# di.net
KiCad netlist of a schematic drawn in Altium Designer
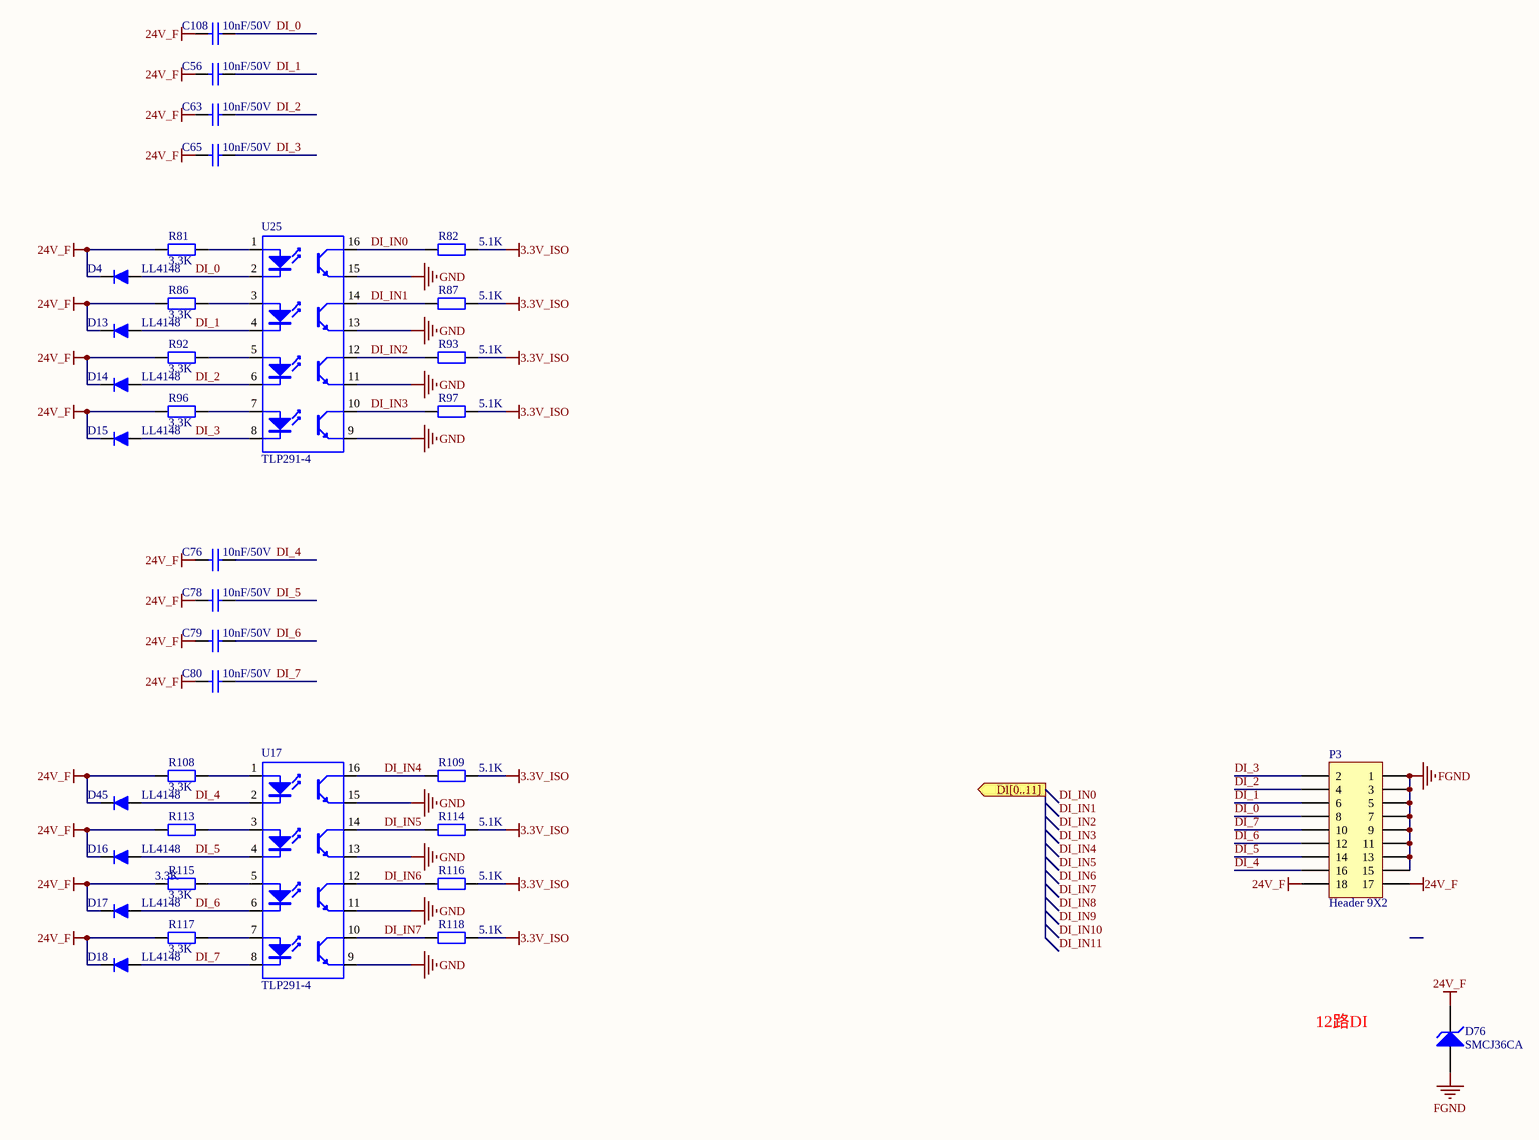
[diagram p0: di.SchDoc]

(export (version "E")
  (design (tool "Eeschema 10.0.6"))
  (components
    (comp (ref "C56")
      (value "10nF/50V")
      (footprint "0603C")
      (description "Capacitor")
      (fields (field (name "PUBLISHER") "Altium Limited"))
      (libsource (lib "Miscellaneous Devices") (part "Cap"))
    )
    (comp (ref "C63")
      (value "10nF/50V")
      (footprint "0603C")
      (description "Capacitor")
      (fields (field (name "PUBLISHER") "Altium Limited"))
      (libsource (lib "Miscellaneous Devices") (part "Cap"))
    )
    (comp (ref "C65")
      (value "10nF/50V")
      (footprint "0603C")
      (description "Capacitor")
      (fields (field (name "PUBLISHER") "Altium Limited"))
      (libsource (lib "Miscellaneous Devices") (part "Cap"))
    )
    (comp (ref "C76")
      (value "10nF/50V")
      (footprint "0603C")
      (description "Capacitor")
      (fields (field (name "PUBLISHER") "Altium Limited"))
      (libsource (lib "Miscellaneous Devices") (part "Cap"))
    )
    (comp (ref "C78")
      (value "10nF/50V")
      (footprint "0603C")
      (description "Capacitor")
      (fields (field (name "PUBLISHER") "Altium Limited"))
      (libsource (lib "Miscellaneous Devices") (part "Cap"))
    )
    (comp (ref "C79")
      (value "10nF/50V")
      (footprint "0603C")
      (description "Capacitor")
      (fields (field (name "PUBLISHER") "Altium Limited"))
      (libsource (lib "Miscellaneous Devices") (part "Cap"))
    )
    (comp (ref "C80")
      (value "10nF/50V")
      (footprint "0603C")
      (description "Capacitor")
      (fields (field (name "PUBLISHER") "Altium Limited"))
      (libsource (lib "Miscellaneous Devices") (part "Cap"))
    )
    (comp (ref "C108")
      (value "10nF/50V")
      (footprint "0603C")
      (description "Capacitor")
      (fields (field (name "PUBLISHER") "Altium Limited"))
      (libsource (lib "Miscellaneous Devices") (part "Cap"))
    )
    (comp (ref "D4")
      (value "LL4148")
      (footprint "DO-213AB/LL34/MiniMELF")
      (description "VISHAY,LL4148,圆柱体MiniMELF100V/2A,ROHS")
      (libsource (lib "Device2018") (part "LL4148"))
    )
    (comp (ref "D13")
      (value "LL4148")
      (footprint "DO-213AB/LL34/MiniMELF")
      (description "VISHAY,LL4148,圆柱体MiniMELF100V/2A,ROHS")
      (libsource (lib "Device2018") (part "LL4148"))
    )
    (comp (ref "D14")
      (value "LL4148")
      (footprint "DO-213AB/LL34/MiniMELF")
      (description "VISHAY,LL4148,圆柱体MiniMELF100V/2A,ROHS")
      (libsource (lib "Device2018") (part "LL4148"))
    )
    (comp (ref "D15")
      (value "LL4148")
      (footprint "DO-213AB/LL34/MiniMELF")
      (description "VISHAY,LL4148,圆柱体MiniMELF100V/2A,ROHS")
      (libsource (lib "Device2018") (part "LL4148"))
    )
    (comp (ref "D16")
      (value "LL4148")
      (footprint "DO-213AB/LL34/MiniMELF")
      (description "VISHAY,LL4148,圆柱体MiniMELF100V/2A,ROHS")
      (libsource (lib "Device2018") (part "LL4148"))
    )
    (comp (ref "D17")
      (value "LL4148")
      (footprint "DO-213AB/LL34/MiniMELF")
      (description "VISHAY,LL4148,圆柱体MiniMELF100V/2A,ROHS")
      (libsource (lib "Device2018") (part "LL4148"))
    )
    (comp (ref "D18")
      (value "LL4148")
      (footprint "DO-213AB/LL34/MiniMELF")
      (description "VISHAY,LL4148,圆柱体MiniMELF100V/2A,ROHS")
      (libsource (lib "Device2018") (part "LL4148"))
    )
    (comp (ref "D45")
      (value "LL4148")
      (footprint "DO-213AB/LL34/MiniMELF")
      (description "VISHAY,LL4148,圆柱体MiniMELF100V/2A,ROHS")
      (libsource (lib "Device2018") (part "LL4148"))
    )
    (comp (ref "D76")
      (value "SMCJ36CA")
      (footprint "smc")
      (description "SMBJ36CA")
      (fields (field (name "PUBLISHER") "Altium Limited"))
      (libsource (lib "Miscellaneous Devices") (part "D Zener"))
    )
    (comp (ref "P3")
      (value "Header 9X2")
      (footprint "XH2.54_2x9")
      (description "Header, 9-Pin, Dual row")
      (fields (field (name "PUBLISHER") "Altium Limited"))
      (libsource (lib "Miscellaneous Connectors") (part "Header 9X2"))
    )
    (comp (ref "R81") (value "3.3K") (footprint "0603R") (libsource (lib "MQlibrary") (part "Res0805M")))
    (comp (ref "R82") (value "5.1K") (footprint "0603R") (libsource (lib "MQlibrary") (part "Res0805M")))
    (comp (ref "R86") (value "3.3K") (footprint "0603R") (libsource (lib "MQlibrary") (part "Res0805M")))
    (comp (ref "R87") (value "5.1K") (footprint "0603R") (libsource (lib "MQlibrary") (part "Res0805M")))
    (comp (ref "R92") (value "3.3K") (footprint "0603R") (libsource (lib "MQlibrary") (part "Res0805M")))
    (comp (ref "R93") (value "5.1K") (footprint "0603R") (libsource (lib "MQlibrary") (part "Res0805M")))
    (comp (ref "R96") (value "3.3K") (footprint "0603R") (libsource (lib "MQlibrary") (part "Res0805M")))
    (comp (ref "R97") (value "5.1K") (footprint "0603R") (libsource (lib "MQlibrary") (part "Res0805M")))
    (comp (ref "R108") (value "3.3K") (footprint "0603R") (libsource (lib "MQlibrary") (part "Res0805M")))
    (comp (ref "R109") (value "5.1K") (footprint "0603R") (libsource (lib "MQlibrary") (part "Res0805M")))
    (comp (ref "R113") (value "3.3K") (footprint "0603R") (libsource (lib "MQlibrary") (part "Res0805M")))
    (comp (ref "R114") (value "5.1K") (footprint "0603R") (libsource (lib "MQlibrary") (part "Res0805M")))
    (comp (ref "R115") (value "3.3K") (footprint "0603R") (libsource (lib "MQlibrary") (part "Res0805M")))
    (comp (ref "R116") (value "5.1K") (footprint "0603R") (libsource (lib "MQlibrary") (part "Res0805M")))
    (comp (ref "R117") (value "3.3K") (footprint "0603R") (libsource (lib "MQlibrary") (part "Res0805M")))
    (comp (ref "R118") (value "5.1K") (footprint "0603R") (libsource (lib "MQlibrary") (part "Res0805M")))
    (comp (ref "U17") (value "TLP291-4") (footprint "SOP16-T") (libsource (lib "DI16") (part "TLP281-4")))
    (comp (ref "U25") (value "TLP291-4") (footprint "SOP16-T") (libsource (lib "DI16") (part "TLP281-4")))
  )
  (nets
    (net (code "14") (name "/DI_0") (class "Default")
      (node (ref "C108") (pin "2") (pinfunction "2_2") (pintype "passive"))
      (node (ref "D4") (pin "1") (pinfunction "2_1") (pintype "passive"))
      (node (ref "P3") (pin "8") (pinfunction "8_8") (pintype "passive"))
      (node (ref "U25") (pin "2") (pinfunction "K_2") (pintype "passive"))
    )
    (net (code "15") (name "/DI_1") (class "Default")
      (node (ref "C56") (pin "2") (pinfunction "2_2") (pintype "passive"))
      (node (ref "D13") (pin "1") (pinfunction "2_1") (pintype "passive"))
      (node (ref "P3") (pin "6") (pinfunction "6_6") (pintype "passive"))
      (node (ref "U25") (pin "4") (pinfunction "K_4") (pintype "passive"))
    )
    (net (code "16") (name "/DI_2") (class "Default")
      (node (ref "C63") (pin "2") (pinfunction "2_2") (pintype "passive"))
      (node (ref "D14") (pin "1") (pinfunction "2_1") (pintype "passive"))
      (node (ref "P3") (pin "4") (pinfunction "4_4") (pintype "passive"))
      (node (ref "U25") (pin "6") (pinfunction "K_6") (pintype "passive"))
    )
    (net (code "17") (name "/DI_3") (class "Default")
      (node (ref "C65") (pin "2") (pinfunction "2_2") (pintype "passive"))
      (node (ref "D15") (pin "1") (pinfunction "2_1") (pintype "passive"))
      (node (ref "P3") (pin "2") (pinfunction "2_2") (pintype "passive"))
      (node (ref "U25") (pin "8") (pinfunction "K_8") (pintype "passive"))
    )
    (net (code "18") (name "/DI_4") (class "Default")
      (node (ref "C76") (pin "2") (pinfunction "2_2") (pintype "passive"))
      (node (ref "D45") (pin "1") (pinfunction "2_1") (pintype "passive"))
      (node (ref "P3") (pin "16") (pinfunction "16_16") (pintype "passive"))
      (node (ref "U17") (pin "2") (pinfunction "K_2") (pintype "passive"))
    )
    (net (code "19") (name "/DI_5") (class "Default")
      (node (ref "C78") (pin "2") (pinfunction "2_2") (pintype "passive"))
      (node (ref "D16") (pin "1") (pinfunction "2_1") (pintype "passive"))
      (node (ref "P3") (pin "14") (pinfunction "14_14") (pintype "passive"))
      (node (ref "U17") (pin "4") (pinfunction "K_4") (pintype "passive"))
    )
    (net (code "20") (name "/DI_6") (class "Default")
      (node (ref "C79") (pin "2") (pinfunction "2_2") (pintype "passive"))
      (node (ref "D17") (pin "1") (pinfunction "2_1") (pintype "passive"))
      (node (ref "P3") (pin "12") (pinfunction "12_12") (pintype "passive"))
      (node (ref "U17") (pin "6") (pinfunction "K_6") (pintype "passive"))
    )
    (net (code "21") (name "/DI_7") (class "Default")
      (node (ref "C80") (pin "2") (pinfunction "2_2") (pintype "passive"))
      (node (ref "D18") (pin "1") (pinfunction "2_1") (pintype "passive"))
      (node (ref "P3") (pin "10") (pinfunction "10_10") (pintype "passive"))
      (node (ref "U17") (pin "8") (pinfunction "K_8") (pintype "passive"))
    )
    (net (code "22") (name "/DI_IN0") (class "Default")
      (node (ref "R82") (pin "2") (pinfunction "2_2") (pintype "passive"))
      (node (ref "U25") (pin "16") (pinfunction "C_16") (pintype "passive"))
    )
    (net (code "23") (name "/DI_IN1") (class "Default")
      (node (ref "R87") (pin "2") (pinfunction "2_2") (pintype "passive"))
      (node (ref "U25") (pin "14") (pinfunction "C_14") (pintype "passive"))
    )
    (net (code "24") (name "/DI_IN2") (class "Default")
      (node (ref "R93") (pin "2") (pinfunction "2_2") (pintype "passive"))
      (node (ref "U25") (pin "12") (pinfunction "C_12") (pintype "passive"))
    )
    (net (code "25") (name "/DI_IN3") (class "Default")
      (node (ref "R97") (pin "2") (pinfunction "2_2") (pintype "passive"))
      (node (ref "U25") (pin "10") (pinfunction "C_10") (pintype "passive"))
    )
    (net (code "26") (name "/DI_IN4") (class "Default")
      (node (ref "R109") (pin "2") (pinfunction "2_2") (pintype "passive"))
      (node (ref "U17") (pin "16") (pinfunction "C_16") (pintype "passive"))
    )
    (net (code "27") (name "/DI_IN5") (class "Default")
      (node (ref "R114") (pin "2") (pinfunction "2_2") (pintype "passive"))
      (node (ref "U17") (pin "14") (pinfunction "C_14") (pintype "passive"))
    )
    (net (code "28") (name "/DI_IN6") (class "Default")
      (node (ref "R116") (pin "2") (pinfunction "2_2") (pintype "passive"))
      (node (ref "U17") (pin "12") (pinfunction "C_12") (pintype "passive"))
    )
    (net (code "29") (name "/DI_IN7") (class "Default")
      (node (ref "R118") (pin "2") (pinfunction "2_2") (pintype "passive"))
      (node (ref "U17") (pin "10") (pinfunction "C_10") (pintype "passive"))
    )
    (net (code "34") (name "3.3V_ISO") (class "Default")
      (node (ref "R109") (pin "1") (pinfunction "1_1") (pintype "passive"))
      (node (ref "R114") (pin "1") (pinfunction "1_1") (pintype "passive"))
      (node (ref "R116") (pin "1") (pinfunction "1_1") (pintype "passive"))
      (node (ref "R118") (pin "1") (pinfunction "1_1") (pintype "passive"))
      (node (ref "R82") (pin "1") (pinfunction "1_1") (pintype "passive"))
      (node (ref "R87") (pin "1") (pinfunction "1_1") (pintype "passive"))
      (node (ref "R93") (pin "1") (pinfunction "1_1") (pintype "passive"))
      (node (ref "R97") (pin "1") (pinfunction "1_1") (pintype "passive"))
    )
    (net (code "35") (name "24V_F") (class "Default")
      (node (ref "C108") (pin "1") (pinfunction "1_1") (pintype "passive"))
      (node (ref "C56") (pin "1") (pinfunction "1_1") (pintype "passive"))
      (node (ref "C63") (pin "1") (pinfunction "1_1") (pintype "passive"))
      (node (ref "C65") (pin "1") (pinfunction "1_1") (pintype "passive"))
      (node (ref "C76") (pin "1") (pinfunction "1_1") (pintype "passive"))
      (node (ref "C78") (pin "1") (pinfunction "1_1") (pintype "passive"))
      (node (ref "C79") (pin "1") (pinfunction "1_1") (pintype "passive"))
      (node (ref "C80") (pin "1") (pinfunction "1_1") (pintype "passive"))
      (node (ref "D13") (pin "2") (pinfunction "1_2") (pintype "passive"))
      (node (ref "D14") (pin "2") (pinfunction "1_2") (pintype "passive"))
      (node (ref "D15") (pin "2") (pinfunction "1_2") (pintype "passive"))
      (node (ref "D16") (pin "2") (pinfunction "1_2") (pintype "passive"))
      (node (ref "D17") (pin "2") (pinfunction "1_2") (pintype "passive"))
      (node (ref "D18") (pin "2") (pinfunction "1_2") (pintype "passive"))
      (node (ref "D4") (pin "2") (pinfunction "1_2") (pintype "passive"))
      (node (ref "D45") (pin "2") (pinfunction "1_2") (pintype "passive"))
      (node (ref "D76") (pin "2") (pinfunction "K_2") (pintype "passive"))
      (node (ref "P3") (pin "17") (pinfunction "17_17") (pintype "passive"))
      (node (ref "P3") (pin "18") (pinfunction "18_18") (pintype "passive"))
      (node (ref "R108") (pin "2") (pinfunction "2_2") (pintype "passive"))
      (node (ref "R113") (pin "2") (pinfunction "2_2") (pintype "passive"))
      (node (ref "R115") (pin "2") (pinfunction "2_2") (pintype "passive"))
      (node (ref "R117") (pin "2") (pinfunction "2_2") (pintype "passive"))
      (node (ref "R81") (pin "2") (pinfunction "2_2") (pintype "passive"))
      (node (ref "R86") (pin "2") (pinfunction "2_2") (pintype "passive"))
      (node (ref "R92") (pin "2") (pinfunction "2_2") (pintype "passive"))
      (node (ref "R96") (pin "2") (pinfunction "2_2") (pintype "passive"))
    )
    (net (code "36") (name "FGND") (class "Default")
      (node (ref "D76") (pin "1") (pinfunction "A_1") (pintype "passive"))
      (node (ref "P3") (pin "1") (pinfunction "1_1") (pintype "passive"))
      (node (ref "P3") (pin "11") (pinfunction "11_11") (pintype "passive"))
      (node (ref "P3") (pin "13") (pinfunction "13_13") (pintype "passive"))
      (node (ref "P3") (pin "15") (pinfunction "15_15") (pintype "passive"))
      (node (ref "P3") (pin "3") (pinfunction "3_3") (pintype "passive"))
      (node (ref "P3") (pin "5") (pinfunction "5_5") (pintype "passive"))
      (node (ref "P3") (pin "7") (pinfunction "7_7") (pintype "passive"))
      (node (ref "P3") (pin "9") (pinfunction "9_9") (pintype "passive"))
    )
    (net (code "37") (name "GND") (class "Default")
      (node (ref "U17") (pin "11") (pinfunction "E_11") (pintype "passive"))
      (node (ref "U17") (pin "13") (pinfunction "E_13") (pintype "passive"))
      (node (ref "U17") (pin "15") (pinfunction "E_15") (pintype "passive"))
      (node (ref "U17") (pin "9") (pinfunction "E_9") (pintype "passive"))
      (node (ref "U25") (pin "11") (pinfunction "E_11") (pintype "passive"))
      (node (ref "U25") (pin "13") (pinfunction "E_13") (pintype "passive"))
      (node (ref "U25") (pin "15") (pinfunction "E_15") (pintype "passive"))
      (node (ref "U25") (pin "9") (pinfunction "E_9") (pintype "passive"))
    )
    (net (code "38") (name "Net-(R81-Pad1)") (class "Default")
      (node (ref "R81") (pin "1") (pinfunction "1_1") (pintype "passive"))
      (node (ref "U25") (pin "1") (pinfunction "A_1") (pintype "passive"))
    )
    (net (code "39") (name "Net-(R86-Pad1)") (class "Default")
      (node (ref "R86") (pin "1") (pinfunction "1_1") (pintype "passive"))
      (node (ref "U25") (pin "3") (pinfunction "A_3") (pintype "passive"))
    )
    (net (code "40") (name "Net-(R92-Pad1)") (class "Default")
      (node (ref "R92") (pin "1") (pinfunction "1_1") (pintype "passive"))
      (node (ref "U25") (pin "5") (pinfunction "A_5") (pintype "passive"))
    )
    (net (code "41") (name "Net-(R96-Pad1)") (class "Default")
      (node (ref "R96") (pin "1") (pinfunction "1_1") (pintype "passive"))
      (node (ref "U25") (pin "7") (pinfunction "A_7") (pintype "passive"))
    )
    (net (code "42") (name "Net-(R108-Pad1)") (class "Default")
      (node (ref "R108") (pin "1") (pinfunction "1_1") (pintype "passive"))
      (node (ref "U17") (pin "1") (pinfunction "A_1") (pintype "passive"))
    )
    (net (code "43") (name "Net-(R113-Pad1)") (class "Default")
      (node (ref "R113") (pin "1") (pinfunction "1_1") (pintype "passive"))
      (node (ref "U17") (pin "3") (pinfunction "A_3") (pintype "passive"))
    )
    (net (code "44") (name "Net-(R115-Pad1)") (class "Default")
      (node (ref "R115") (pin "1") (pinfunction "1_1") (pintype "passive"))
      (node (ref "U17") (pin "5") (pinfunction "A_5") (pintype "passive"))
    )
    (net (code "45") (name "Net-(R117-Pad1)") (class "Default")
      (node (ref "R117") (pin "1") (pinfunction "1_1") (pintype "passive"))
      (node (ref "U17") (pin "7") (pinfunction "A_7") (pintype "passive"))
    )
  )
)
